# RoomBug.net
KiCad netlist of a schematic drawn in Altium Designer
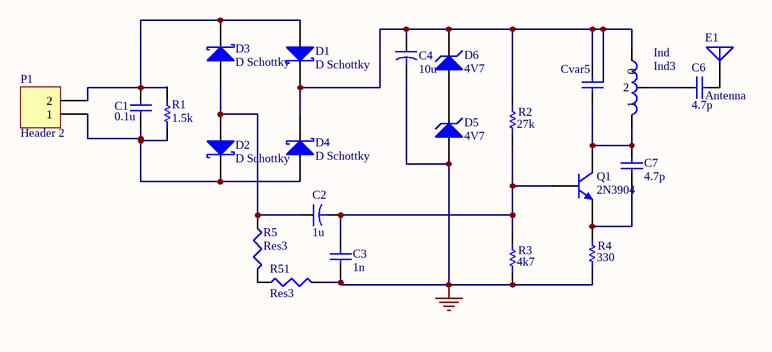
[diagram p0: RoomBug.SCHDOC]

(export (version "E")
  (design (tool "Eeschema 10.0.6"))
  (components
    (comp (ref "C1")
      (value "0.1u")
      (footprint "RAD-0.3")
      (description "Capacitor")
      (fields (field (name "PUBLISHER") "Altium Limited"))
      (libsource (lib "Miscellaneous Devices") (part "Cap"))
    )
    (comp (ref "C2")
      (value "1u")
      (footprint "CAPR5-4X5")
      (description "Capacitor")
      (fields (field (name "PUBLISHER") "Altium Limited"))
      (libsource (lib "Miscellaneous Devices") (part "Cap2"))
    )
    (comp (ref "C3")
      (value "1n")
      (footprint "RAD-0.3")
      (description "Capacitor")
      (fields (field (name "PUBLISHER") "Altium Limited"))
      (libsource (lib "Miscellaneous Devices") (part "Cap"))
    )
    (comp (ref "C4")
      (value "10u")
      (footprint "CAPR5-4X5")
      (description "Capacitor")
      (fields (field (name "PUBLISHER") "Altium Limited"))
      (libsource (lib "Miscellaneous Devices") (part "Cap2"))
    )
    (comp (ref "C6")
      (value "4.7p")
      (footprint "RAD-0.3")
      (description "Capacitor")
      (fields (field (name "PUBLISHER") "Altium Limited"))
      (libsource (lib "Miscellaneous Devices") (part "Cap"))
    )
    (comp (ref "C7")
      (value "4.7p")
      (footprint "RAD-0.3")
      (description "Capacitor")
      (fields (field (name "PUBLISHER") "Altium Limited"))
      (libsource (lib "Miscellaneous Devices") (part "Cap"))
    )
    (comp (ref "Cvar5") (value "2-20p") (footprint "CapVarAmarillo") (libsource (lib "epf") (part "CapVar1")))
    (comp (ref "D1")
      (value "D Schottky")
      (footprint "DSO-C2/X2.3")
      (description "Schottky Diode")
      (fields (field (name "PUBLISHER") "Altium Limited"))
      (libsource (lib "Miscellaneous Devices") (part "D Schottky"))
    )
    (comp (ref "D2")
      (value "D Schottky")
      (footprint "DSO-C2/X2.3")
      (description "Schottky Diode")
      (fields (field (name "PUBLISHER") "Altium Limited"))
      (libsource (lib "Miscellaneous Devices") (part "D Schottky"))
    )
    (comp (ref "D3")
      (value "D Schottky")
      (footprint "DSO-C2/X2.3")
      (description "Schottky Diode")
      (fields (field (name "PUBLISHER") "Altium Limited"))
      (libsource (lib "Miscellaneous Devices") (part "D Schottky"))
    )
    (comp (ref "D4")
      (value "D Schottky")
      (footprint "DSO-C2/X2.3")
      (description "Schottky Diode")
      (fields (field (name "PUBLISHER") "Altium Limited"))
      (libsource (lib "Miscellaneous Devices") (part "D Schottky"))
    )
    (comp (ref "D5")
      (value "4V7")
      (footprint "DIODE-0.7")
      (description "Zener Diode")
      (fields (field (name "PUBLISHER") "Altium Limited"))
      (libsource (lib "Miscellaneous Devices") (part "D Zener"))
    )
    (comp (ref "D6")
      (value "4V7")
      (footprint "DIODE-0.7")
      (description "Zener Diode")
      (fields (field (name "PUBLISHER") "Altium Limited"))
      (libsource (lib "Miscellaneous Devices") (part "D Zener"))
    )
    (comp (ref "E1")
      (value "Antenna")
      (footprint "PIN1")
      (description "Generic Antenna")
      (fields (field (name "PUBLISHER") "Altium Limited"))
      (libsource (lib "Miscellaneous Devices") (part "Antenna"))
    )
    (comp (ref "Ind") (value "Ind3") (footprint "Ind 7mm") (libsource (lib "epf") (part "Ind3")))
    (comp (ref "P1")
      (value "Header 2")
      (footprint "HDR1X2")
      (description "Header, 2-Pin")
      (fields (field (name "PUBLISHER") "Altium Limited"))
      (libsource (lib "Miscellaneous Connectors") (part "Header 2"))
    )
    (comp (ref "Q1")
      (value "2N3904")
      (footprint "TO-92A")
      (description "NPN General Purpose Amplifier")
      (fields (field (name "PUBLISHER") "Altium Limited"))
      (libsource (lib "FSC Discrete BJT") (part "2N3904"))
    )
    (comp (ref "R1")
      (value "1.5k")
      (footprint "AXIAL-0.3")
      (description "Resistor")
      (fields (field (name "PUBLISHER") "Altium Limited"))
      (libsource (lib "Miscellaneous Devices") (part "Res1"))
    )
    (comp (ref "R2")
      (value "27k")
      (footprint "AXIAL-0.3")
      (description "Resistor")
      (fields (field (name "PUBLISHER") "Altium Limited"))
      (libsource (lib "Miscellaneous Devices") (part "Res1"))
    )
    (comp (ref "R3")
      (value "4k7")
      (footprint "AXIAL-0.3")
      (description "Resistor")
      (fields (field (name "PUBLISHER") "Altium Limited"))
      (libsource (lib "Miscellaneous Devices") (part "Res1"))
    )
    (comp (ref "R4")
      (value "330")
      (footprint "AXIAL-0.3")
      (description "Resistor")
      (fields (field (name "PUBLISHER") "Altium Limited"))
      (libsource (lib "Miscellaneous Devices") (part "Res1"))
    )
    (comp (ref "R5")
      (value "Res3")
      (footprint "CR1608-0603")
      (description "Resistor")
      (fields (field (name "PUBLISHER") "Altium Limited"))
      (libsource (lib "Miscellaneous Devices") (part "Res3"))
    )
    (comp (ref "R51")
      (value "Res3")
      (footprint "CR1608-0603")
      (description "Resistor")
      (fields (field (name "PUBLISHER") "Altium Limited"))
      (libsource (lib "Miscellaneous Devices") (part "Res3"))
    )
  )
  (nets
    (net (code "1") (name "GND") (class "Default")
      (node (ref "C3") (pin "1") (pinfunction "1_1") (pintype "passive"))
      (node (ref "C4") (pin "2") (pinfunction "2_2") (pintype "passive"))
      (node (ref "D5") (pin "1") (pinfunction "A_1") (pintype "passive"))
      (node (ref "R3") (pin "1") (pinfunction "1_1") (pintype "passive"))
      (node (ref "R4") (pin "1") (pinfunction "1_1") (pintype "passive"))
      (node (ref "R51") (pin "2") (pinfunction "2_2") (pintype "passive"))
    )
    (net (code "2") (name "Net-(C6-Pad2)") (class "Default")
      (node (ref "C6") (pin "2") (pinfunction "2_2") (pintype "passive"))
      (node (ref "Ind") (pin "2") (pinfunction "2_2") (pintype "passive"))
    )
    (net (code "3") (name "Net-(D1-A)") (class "Default")
      (node (ref "C1") (pin "2") (pinfunction "2_2") (pintype "passive"))
      (node (ref "D1") (pin "1") (pinfunction "A_1") (pintype "passive"))
      (node (ref "D3") (pin "2") (pinfunction "K_2") (pintype "passive"))
      (node (ref "P1") (pin "2") (pinfunction "2_2") (pintype "passive"))
      (node (ref "R1") (pin "2") (pinfunction "2_2") (pintype "passive"))
    )
    (net (code "4") (name "Net-(D1-K)") (class "Default")
      (node (ref "C4") (pin "1") (pinfunction "1_1") (pintype "passive"))
      (node (ref "Cvar5") (pin "2") (pinfunction "2_2") (pintype "passive"))
      (node (ref "Cvar5") (pin "3") (pinfunction "3_3") (pintype "passive"))
      (node (ref "D1") (pin "2") (pinfunction "K_2") (pintype "passive"))
      (node (ref "D4") (pin "2") (pinfunction "K_2") (pintype "passive"))
      (node (ref "D6") (pin "2") (pinfunction "K_2") (pintype "passive"))
      (node (ref "Ind") (pin "0") (pinfunction "0_0") (pintype "passive"))
      (node (ref "R2") (pin "2") (pinfunction "2_2") (pintype "passive"))
    )
    (net (code "5") (name "Net-(D2-A)") (class "Default")
      (node (ref "C2") (pin "1") (pinfunction "1_1") (pintype "passive"))
      (node (ref "D2") (pin "1") (pinfunction "A_1") (pintype "passive"))
      (node (ref "D3") (pin "1") (pinfunction "A_1") (pintype "passive"))
      (node (ref "R5") (pin "1") (pinfunction "1_1") (pintype "passive"))
    )
    (net (code "6") (name "Net-(D2-K)") (class "Default")
      (node (ref "C1") (pin "1") (pinfunction "1_1") (pintype "passive"))
      (node (ref "D2") (pin "2") (pinfunction "K_2") (pintype "passive"))
      (node (ref "D4") (pin "1") (pinfunction "A_1") (pintype "passive"))
      (node (ref "P1") (pin "1") (pinfunction "1_1") (pintype "passive"))
      (node (ref "R1") (pin "1") (pinfunction "1_1") (pintype "passive"))
    )
    (net (code "7") (name "Net-(D5-K)") (class "Default")
      (node (ref "D5") (pin "2") (pinfunction "K_2") (pintype "passive"))
      (node (ref "D6") (pin "1") (pinfunction "A_1") (pintype "passive"))
    )
    (net (code "8") (name "Net-(E1-A)") (class "Default")
      (node (ref "C6") (pin "1") (pinfunction "1_1") (pintype "passive"))
      (node (ref "E1") (pin "1") (pinfunction "A_1") (pintype "passive"))
    )
    (net (code "9") (name "Net-(Q1-B)") (class "Default")
      (node (ref "C2") (pin "2") (pinfunction "2_2") (pintype "passive"))
      (node (ref "C3") (pin "2") (pinfunction "2_2") (pintype "passive"))
      (node (ref "Q1") (pin "2") (pinfunction "B_2") (pintype "passive"))
      (node (ref "R2") (pin "1") (pinfunction "1_1") (pintype "passive"))
      (node (ref "R3") (pin "2") (pinfunction "2_2") (pintype "passive"))
    )
    (net (code "10") (name "Net-(Q1-C)") (class "Default")
      (node (ref "C7") (pin "2") (pinfunction "2_2") (pintype "passive"))
      (node (ref "Cvar5") (pin "1") (pinfunction "1_1") (pintype "passive"))
      (node (ref "Ind") (pin "1") (pinfunction "1_1") (pintype "passive"))
      (node (ref "Q1") (pin "3") (pinfunction "C_3") (pintype "passive"))
    )
    (net (code "11") (name "Net-(Q1-E)") (class "Default")
      (node (ref "C7") (pin "1") (pinfunction "1_1") (pintype "passive"))
      (node (ref "Q1") (pin "1") (pinfunction "E_1") (pintype "passive"))
      (node (ref "R4") (pin "2") (pinfunction "2_2") (pintype "passive"))
    )
    (net (code "12") (name "Net-(R5-Pad2)") (class "Default")
      (node (ref "R5") (pin "2") (pinfunction "2_2") (pintype "passive"))
      (node (ref "R51") (pin "1") (pinfunction "1_1") (pintype "passive"))
    )
  )
)
